# ASD2303.net
KiCad netlist of a schematic drawn in EAGLE
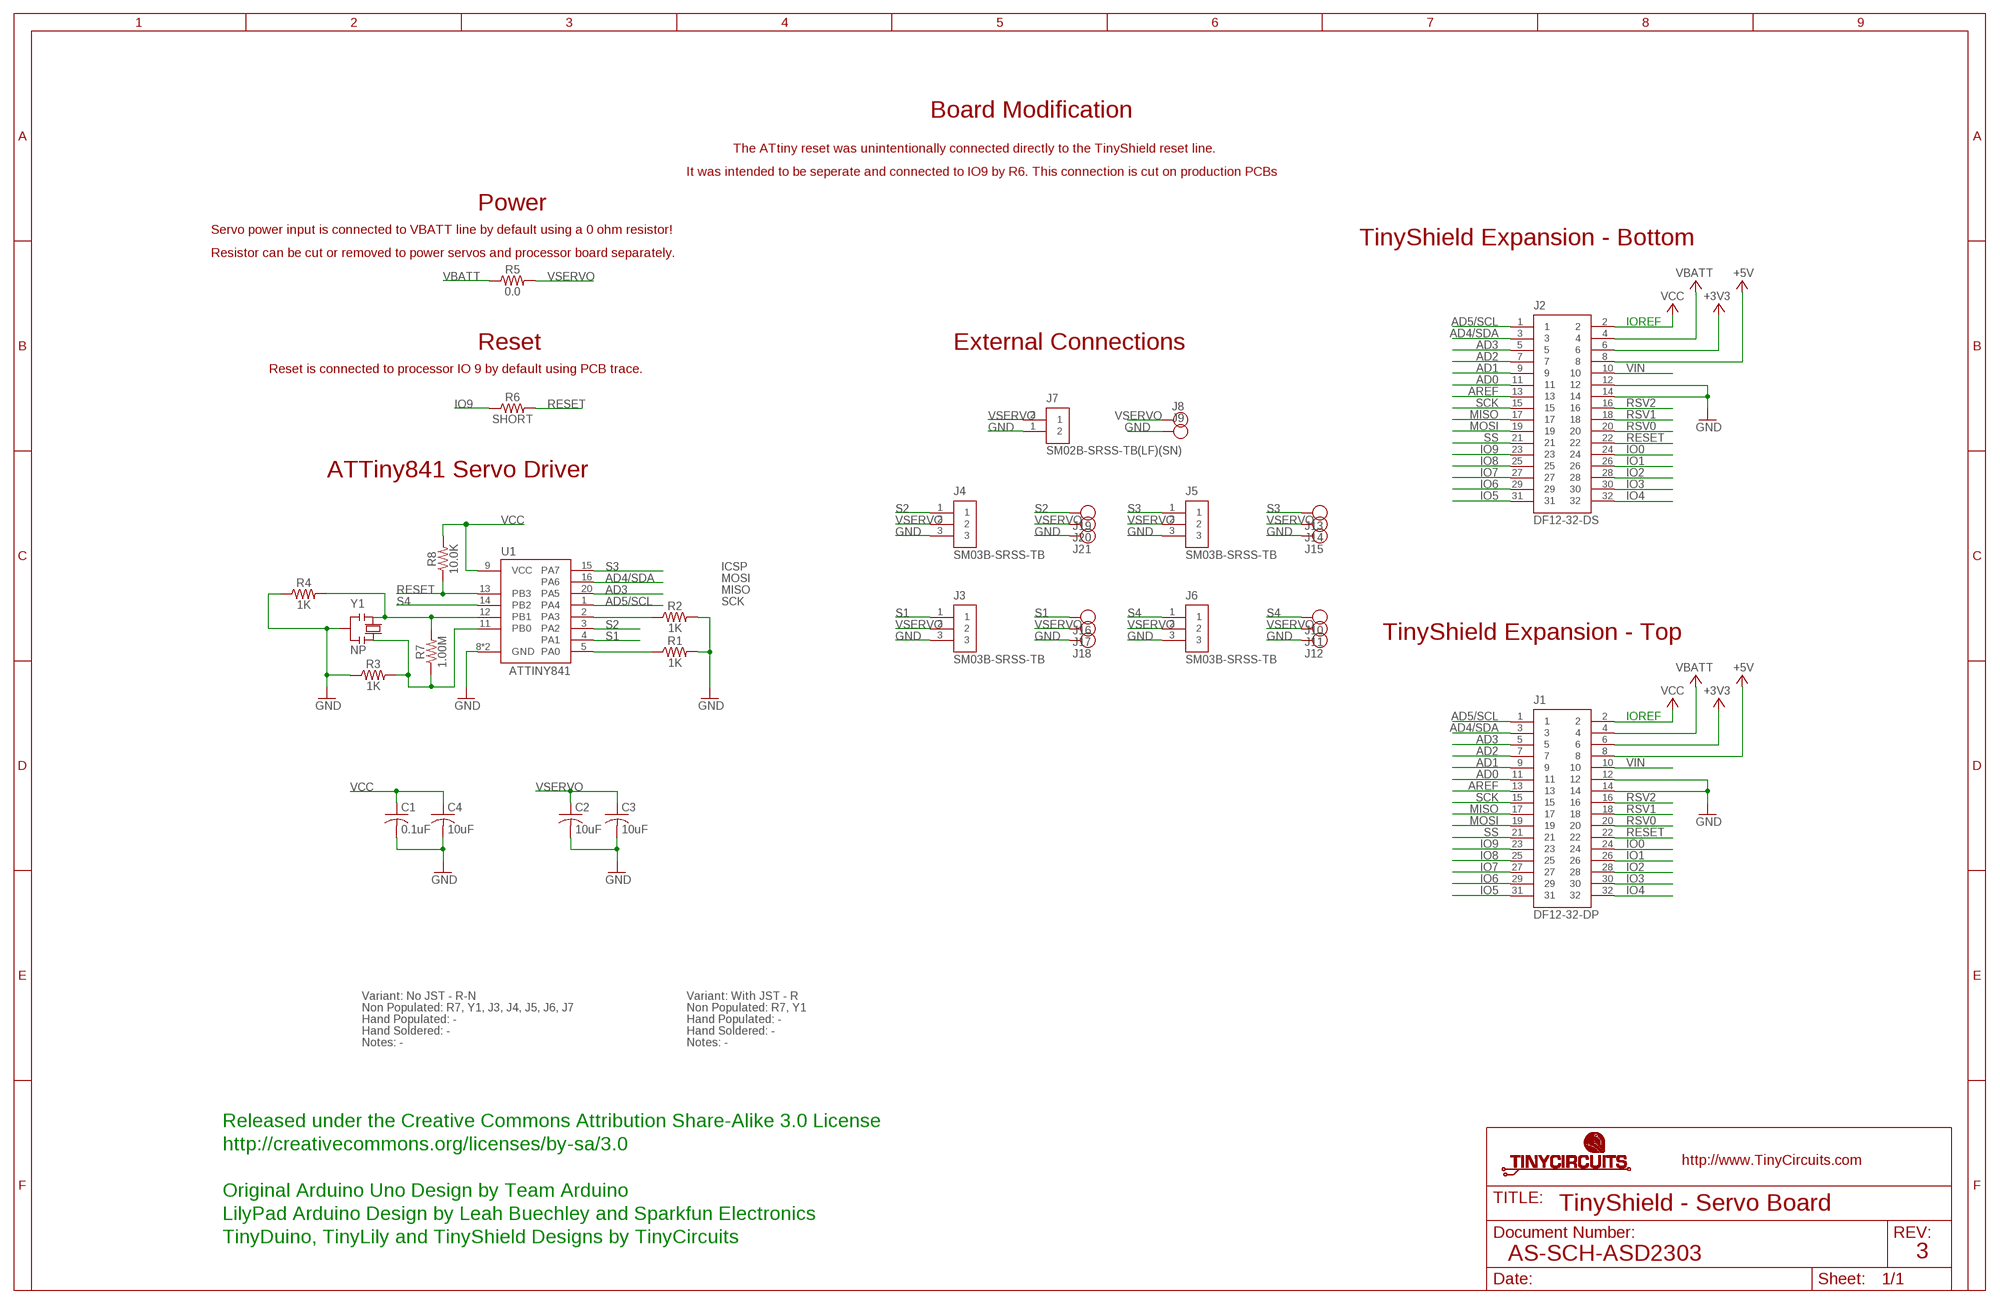
[diagram p0: schematic, sheet 1]

(export (version "E")
  (design (tool "Eeschema 10.0.6"))
  (components
    (comp (ref "C1")
      (value "0.1uF")
      (footprint "eagle-import:C0402")
      (fields (field (name "PARTNO") "AS-ITM-00008"))
      (libsource (lib "eagle-import") (part "AS-ITM-00008"))
    )
    (comp (ref "C2")
      (value "10uF")
      (footprint "eagle-import:C0805")
      (fields (field (name "PARTNO") "AS-ITM-00045"))
      (libsource (lib "eagle-import") (part "AS-ITM-00045"))
    )
    (comp (ref "C3")
      (value "10uF")
      (footprint "eagle-import:C0805")
      (fields (field (name "PARTNO") "AS-ITM-00045"))
      (libsource (lib "eagle-import") (part "AS-ITM-00045"))
    )
    (comp (ref "C4")
      (value "10uF")
      (footprint "eagle-import:C0805")
      (fields (field (name "PARTNO") "AS-ITM-00045"))
      (libsource (lib "eagle-import") (part "AS-ITM-00045"))
    )
    (comp (ref "J1")
      (value "DF12-32-DP")
      (footprint "eagle-import:DF12-32-DP")
      (fields (field (name "PARTNO") "AS-ITM-00015") (field (name "PARTNO_1") "AS-ITM-00015"))
      (libsource (lib "eagle-import") (part "AS-ITM-00015"))
    )
    (comp (ref "J2")
      (value "DF12-32-DS")
      (footprint "eagle-import:DF12-32-DS")
      (fields (field (name "PARTNO") "AS-ITM-00012") (field (name "PARTNO_1") "AS-ITM-00012"))
      (libsource (lib "eagle-import") (part "AS-ITM-00012"))
    )
    (comp (ref "J3")
      (value "SM03B-SRSS-TB")
      (footprint "eagle-import:JST_SH_3X1")
      (fields (field (name "PARTNO") "AS-ITM-00244"))
      (libsource (lib "eagle-import") (part "AS-ITM-00244"))
    )
    (comp (ref "J4")
      (value "SM03B-SRSS-TB")
      (footprint "eagle-import:JST_SH_3X1")
      (fields (field (name "PARTNO") "AS-ITM-00244"))
      (libsource (lib "eagle-import") (part "AS-ITM-00244"))
    )
    (comp (ref "J5")
      (value "SM03B-SRSS-TB")
      (footprint "eagle-import:JST_SH_3X1")
      (fields (field (name "PARTNO") "AS-ITM-00244"))
      (libsource (lib "eagle-import") (part "AS-ITM-00244"))
    )
    (comp (ref "J6")
      (value "SM03B-SRSS-TB")
      (footprint "eagle-import:JST_SH_3X1")
      (fields (field (name "PARTNO") "AS-ITM-00244"))
      (libsource (lib "eagle-import") (part "AS-ITM-00244"))
    )
    (comp (ref "J7")
      (value "SM02B-SRSS-TB(LF)(SN)")
      (footprint "eagle-import:JST_SH_2X1")
      (fields (field (name "PARTNO") "AS-ITM-00231"))
      (libsource (lib "eagle-import") (part "AS-ITM-00231"))
    )
    (comp (ref "J8")
      (value "PIN_1X.1\"1")
      (footprint "eagle-import:1X.1__2")
      (libsource (lib "eagle-import") (part "PIN_1X.1{dblquote}1"))
    )
    (comp (ref "J9")
      (value "PIN_1X.1\"1")
      (footprint "eagle-import:1X.1__2")
      (libsource (lib "eagle-import") (part "PIN_1X.1{dblquote}1"))
    )
    (comp (ref "J10")
      (value "PIN_1X.1\"1")
      (footprint "eagle-import:1X.1__2")
      (libsource (lib "eagle-import") (part "PIN_1X.1{dblquote}1"))
    )
    (comp (ref "J11")
      (value "PIN_1X.1\"1")
      (footprint "eagle-import:1X.1__2")
      (libsource (lib "eagle-import") (part "PIN_1X.1{dblquote}1"))
    )
    (comp (ref "J12")
      (value "PIN_1X.1\"1")
      (footprint "eagle-import:1X.1__2")
      (libsource (lib "eagle-import") (part "PIN_1X.1{dblquote}1"))
    )
    (comp (ref "J13")
      (value "PIN_1X.1\"1")
      (footprint "eagle-import:1X.1__2")
      (libsource (lib "eagle-import") (part "PIN_1X.1{dblquote}1"))
    )
    (comp (ref "J14")
      (value "PIN_1X.1\"1")
      (footprint "eagle-import:1X.1__2")
      (libsource (lib "eagle-import") (part "PIN_1X.1{dblquote}1"))
    )
    (comp (ref "J15")
      (value "PIN_1X.1\"1")
      (footprint "eagle-import:1X.1__2")
      (libsource (lib "eagle-import") (part "PIN_1X.1{dblquote}1"))
    )
    (comp (ref "J16")
      (value "PIN_1X.1\"1")
      (footprint "eagle-import:1X.1__2")
      (libsource (lib "eagle-import") (part "PIN_1X.1{dblquote}1"))
    )
    (comp (ref "J17")
      (value "PIN_1X.1\"1")
      (footprint "eagle-import:1X.1__2")
      (libsource (lib "eagle-import") (part "PIN_1X.1{dblquote}1"))
    )
    (comp (ref "J18")
      (value "PIN_1X.1\"1")
      (footprint "eagle-import:1X.1__2")
      (libsource (lib "eagle-import") (part "PIN_1X.1{dblquote}1"))
    )
    (comp (ref "J19")
      (value "PIN_1X.1\"1")
      (footprint "eagle-import:1X.1__2")
      (libsource (lib "eagle-import") (part "PIN_1X.1{dblquote}1"))
    )
    (comp (ref "J20")
      (value "PIN_1X.1\"1")
      (footprint "eagle-import:1X.1__2")
      (libsource (lib "eagle-import") (part "PIN_1X.1{dblquote}1"))
    )
    (comp (ref "J21")
      (value "PIN_1X.1\"1")
      (footprint "eagle-import:1X.1__2")
      (libsource (lib "eagle-import") (part "PIN_1X.1{dblquote}1"))
    )
    (comp (ref "R1")
      (value "1K")
      (footprint "eagle-import:0402")
      (fields (field (name "PARTNO") "AS-ITM-00003") (field (name "PARTNO_1") "AS-ITM-00003"))
      (libsource (lib "eagle-import") (part "AS-ITM-00003"))
    )
    (comp (ref "R2")
      (value "1K")
      (footprint "eagle-import:0402")
      (fields (field (name "PARTNO") "AS-ITM-00003") (field (name "PARTNO_1") "AS-ITM-00003"))
      (libsource (lib "eagle-import") (part "AS-ITM-00003"))
    )
    (comp (ref "R3")
      (value "1K")
      (footprint "eagle-import:0402")
      (fields (field (name "PARTNO") "AS-ITM-00003") (field (name "PARTNO_1") "AS-ITM-00003"))
      (libsource (lib "eagle-import") (part "AS-ITM-00003"))
    )
    (comp (ref "R4")
      (value "1K")
      (footprint "eagle-import:0402")
      (fields (field (name "PARTNO") "AS-ITM-00003") (field (name "PARTNO_1") "AS-ITM-00003"))
      (libsource (lib "eagle-import") (part "AS-ITM-00003"))
    )
    (comp (ref "R5")
      (value "0.0")
      (footprint "eagle-import:0402")
      (fields (field (name "PARTNO") "AS-ITM-00076"))
      (libsource (lib "eagle-import") (part "AS-ITM-00076"))
    )
    (comp (ref "R6")
      (value "SHORT")
      (footprint "eagle-import:0402_SHORT")
      (libsource (lib "eagle-import") (part "AS-ITM-000760402_SHORT"))
    )
    (comp (ref "R7")
      (value "1.00M")
      (footprint "eagle-import:0402")
      (fields (field (name "PARTNO") "AS-ITM-00005"))
      (libsource (lib "eagle-import") (part "AS-ITM-00005"))
    )
    (comp (ref "R8")
      (value "10.0K")
      (footprint "eagle-import:0402")
      (fields (field (name "PARTNO") "AS-ITM-00032"))
      (libsource (lib "eagle-import") (part "AS-ITM-00032"))
    )
    (comp (ref "U1")
      (value "ATTINY841")
      (footprint "eagle-import:VQFN-20")
      (fields (field (name "PARTNO") "AS-ITM-00255"))
      (libsource (lib "eagle-import") (part "AS-ITM-00255"))
    )
    (comp (ref "Y1")
      (value "NP")
      (footprint "eagle-import:RESONATOR_SMALL")
      (fields (field (name "PARTNO") "AS-ITM-00027") (field (name "PARTNO_1") "AS-ITM-00027"))
      (libsource (lib "eagle-import") (part "AS-ITM-00027B"))
    )
  )
  (nets
    (net (code "1") (name "+3V3") (class "Default")
      (node (ref "J1") (pin "6") (pinfunction "6_6") (pintype "bidirectional"))
      (node (ref "J2") (pin "6") (pinfunction "6_6") (pintype "bidirectional"))
    )
    (net (code "2") (name "+5V") (class "Default")
      (node (ref "J1") (pin "8") (pinfunction "8_8") (pintype "bidirectional"))
      (node (ref "J2") (pin "8") (pinfunction "8_8") (pintype "bidirectional"))
    )
    (net (code "3") (name "/AD0") (class "Default")
      (node (ref "J1") (pin "11") (pinfunction "11_11") (pintype "bidirectional"))
      (node (ref "J2") (pin "11") (pinfunction "11_11") (pintype "bidirectional"))
    )
    (net (code "4") (name "/AD1") (class "Default")
      (node (ref "J1") (pin "9") (pinfunction "9_9") (pintype "bidirectional"))
      (node (ref "J2") (pin "9") (pinfunction "9_9") (pintype "bidirectional"))
    )
    (net (code "5") (name "/AD2") (class "Default")
      (node (ref "J1") (pin "7") (pinfunction "7_7") (pintype "bidirectional"))
      (node (ref "J2") (pin "7") (pinfunction "7_7") (pintype "bidirectional"))
    )
    (net (code "6") (name "/AD3") (class "Default")
      (node (ref "J1") (pin "5") (pinfunction "5_5") (pintype "bidirectional"))
      (node (ref "J2") (pin "5") (pinfunction "5_5") (pintype "bidirectional"))
      (node (ref "U1") (pin "20") (pinfunction "PA5_20") (pintype "bidirectional"))
    )
    (net (code "7") (name "/AD4{slash}SDA") (class "Default")
      (node (ref "J1") (pin "3") (pinfunction "3_3") (pintype "bidirectional"))
      (node (ref "J2") (pin "3") (pinfunction "3_3") (pintype "bidirectional"))
      (node (ref "U1") (pin "16") (pinfunction "PA6_16") (pintype "bidirectional"))
    )
    (net (code "8") (name "/AD5{slash}SCL") (class "Default")
      (node (ref "J1") (pin "1") (pinfunction "1_1") (pintype "bidirectional"))
      (node (ref "J2") (pin "1") (pinfunction "1_1") (pintype "bidirectional"))
      (node (ref "U1") (pin "1") (pinfunction "PA4_1") (pintype "bidirectional"))
    )
    (net (code "9") (name "/AREF") (class "Default")
      (node (ref "J1") (pin "13") (pinfunction "13_13") (pintype "bidirectional"))
      (node (ref "J2") (pin "13") (pinfunction "13_13") (pintype "bidirectional"))
    )
    (net (code "10") (name "/IO0") (class "Default")
      (node (ref "J1") (pin "24") (pinfunction "24_24") (pintype "bidirectional"))
      (node (ref "J2") (pin "24") (pinfunction "24_24") (pintype "bidirectional"))
    )
    (net (code "11") (name "/IO1") (class "Default")
      (node (ref "J1") (pin "26") (pinfunction "26_26") (pintype "bidirectional"))
      (node (ref "J2") (pin "26") (pinfunction "26_26") (pintype "bidirectional"))
    )
    (net (code "12") (name "/IO2") (class "Default")
      (node (ref "J1") (pin "28") (pinfunction "28_28") (pintype "bidirectional"))
      (node (ref "J2") (pin "28") (pinfunction "28_28") (pintype "bidirectional"))
    )
    (net (code "13") (name "/IO3") (class "Default")
      (node (ref "J1") (pin "30") (pinfunction "30_30") (pintype "bidirectional"))
      (node (ref "J2") (pin "30") (pinfunction "30_30") (pintype "bidirectional"))
    )
    (net (code "14") (name "/IO4") (class "Default")
      (node (ref "J1") (pin "32") (pinfunction "32_32") (pintype "bidirectional"))
      (node (ref "J2") (pin "32") (pinfunction "32_32") (pintype "bidirectional"))
    )
    (net (code "15") (name "/IO5") (class "Default")
      (node (ref "J1") (pin "31") (pinfunction "31_31") (pintype "bidirectional"))
      (node (ref "J2") (pin "31") (pinfunction "31_31") (pintype "bidirectional"))
    )
    (net (code "16") (name "/IO6") (class "Default")
      (node (ref "J1") (pin "29") (pinfunction "29_29") (pintype "bidirectional"))
      (node (ref "J2") (pin "29") (pinfunction "29_29") (pintype "bidirectional"))
    )
    (net (code "17") (name "/IO7") (class "Default")
      (node (ref "J1") (pin "27") (pinfunction "27_27") (pintype "bidirectional"))
      (node (ref "J2") (pin "27") (pinfunction "27_27") (pintype "bidirectional"))
    )
    (net (code "18") (name "/IO8") (class "Default")
      (node (ref "J1") (pin "25") (pinfunction "25_25") (pintype "bidirectional"))
      (node (ref "J2") (pin "25") (pinfunction "25_25") (pintype "bidirectional"))
    )
    (net (code "19") (name "/IO9") (class "Default")
      (node (ref "J1") (pin "23") (pinfunction "23_23") (pintype "bidirectional"))
      (node (ref "J2") (pin "23") (pinfunction "23_23") (pintype "bidirectional"))
      (node (ref "R6") (pin "1") (pinfunction "1_1") (pintype "passive"))
    )
    (net (code "20") (name "/MISO") (class "Default")
      (node (ref "J1") (pin "17") (pinfunction "17_17") (pintype "bidirectional"))
      (node (ref "J2") (pin "17") (pinfunction "17_17") (pintype "bidirectional"))
    )
    (net (code "21") (name "/MOSI") (class "Default")
      (node (ref "J1") (pin "19") (pinfunction "19_19") (pintype "bidirectional"))
      (node (ref "J2") (pin "19") (pinfunction "19_19") (pintype "bidirectional"))
    )
    (net (code "22") (name "/RESET") (class "Default")
      (node (ref "J1") (pin "22") (pinfunction "22_22") (pintype "bidirectional"))
      (node (ref "J2") (pin "22") (pinfunction "22_22") (pintype "bidirectional"))
      (node (ref "R6") (pin "2") (pinfunction "2_2") (pintype "passive"))
      (node (ref "R8") (pin "1") (pinfunction "1_1") (pintype "passive"))
      (node (ref "U1") (pin "13") (pinfunction "PB3_13") (pintype "bidirectional"))
    )
    (net (code "23") (name "/RSV0") (class "Default")
      (node (ref "J1") (pin "20") (pinfunction "20_20") (pintype "bidirectional"))
      (node (ref "J2") (pin "20") (pinfunction "20_20") (pintype "bidirectional"))
    )
    (net (code "24") (name "/RSV1") (class "Default")
      (node (ref "J1") (pin "18") (pinfunction "18_18") (pintype "bidirectional"))
      (node (ref "J2") (pin "18") (pinfunction "18_18") (pintype "bidirectional"))
    )
    (net (code "25") (name "/RSV2") (class "Default")
      (node (ref "J1") (pin "16") (pinfunction "16_16") (pintype "bidirectional"))
      (node (ref "J2") (pin "16") (pinfunction "16_16") (pintype "bidirectional"))
    )
    (net (code "26") (name "/S1") (class "Default")
      (node (ref "J16") (pin "1") (pinfunction "1_1") (pintype "bidirectional"))
      (node (ref "J3") (pin "1") (pinfunction "1_1") (pintype "bidirectional"))
      (node (ref "U1") (pin "4") (pinfunction "PA1_4") (pintype "bidirectional"))
    )
    (net (code "27") (name "/S2") (class "Default")
      (node (ref "J19") (pin "1") (pinfunction "1_1") (pintype "bidirectional"))
      (node (ref "J4") (pin "1") (pinfunction "1_1") (pintype "bidirectional"))
      (node (ref "U1") (pin "3") (pinfunction "PA2_3") (pintype "bidirectional"))
    )
    (net (code "28") (name "/S3") (class "Default")
      (node (ref "J13") (pin "1") (pinfunction "1_1") (pintype "bidirectional"))
      (node (ref "J5") (pin "1") (pinfunction "1_1") (pintype "bidirectional"))
      (node (ref "U1") (pin "15") (pinfunction "PA7_15") (pintype "bidirectional"))
    )
    (net (code "29") (name "/S4") (class "Default")
      (node (ref "J10") (pin "1") (pinfunction "1_1") (pintype "bidirectional"))
      (node (ref "J6") (pin "1") (pinfunction "1_1") (pintype "bidirectional"))
      (node (ref "U1") (pin "14") (pinfunction "PB2_14") (pintype "bidirectional"))
    )
    (net (code "30") (name "/SCK") (class "Default")
      (node (ref "J1") (pin "15") (pinfunction "15_15") (pintype "bidirectional"))
      (node (ref "J2") (pin "15") (pinfunction "15_15") (pintype "bidirectional"))
    )
    (net (code "31") (name "/SS") (class "Default")
      (node (ref "J1") (pin "21") (pinfunction "21_21") (pintype "bidirectional"))
      (node (ref "J2") (pin "21") (pinfunction "21_21") (pintype "bidirectional"))
    )
    (net (code "32") (name "/VIN") (class "Default")
      (node (ref "J1") (pin "10") (pinfunction "10_10") (pintype "bidirectional"))
      (node (ref "J2") (pin "10") (pinfunction "10_10") (pintype "bidirectional"))
    )
    (net (code "33") (name "/VSERVO") (class "Default")
      (node (ref "C2") (pin "1") (pinfunction "1_1") (pintype "passive"))
      (node (ref "C3") (pin "1") (pinfunction "1_1") (pintype "passive"))
      (node (ref "J11") (pin "1") (pinfunction "1_1") (pintype "bidirectional"))
      (node (ref "J14") (pin "1") (pinfunction "1_1") (pintype "bidirectional"))
      (node (ref "J17") (pin "1") (pinfunction "1_1") (pintype "bidirectional"))
      (node (ref "J20") (pin "1") (pinfunction "1_1") (pintype "bidirectional"))
      (node (ref "J3") (pin "2") (pinfunction "2_2") (pintype "bidirectional"))
      (node (ref "J4") (pin "2") (pinfunction "2_2") (pintype "bidirectional"))
      (node (ref "J5") (pin "2") (pinfunction "2_2") (pintype "bidirectional"))
      (node (ref "J6") (pin "2") (pinfunction "2_2") (pintype "bidirectional"))
      (node (ref "J7") (pin "2") (pinfunction "1_2") (pintype "bidirectional"))
      (node (ref "J8") (pin "1") (pinfunction "1_1") (pintype "bidirectional"))
      (node (ref "R5") (pin "2") (pinfunction "2_2") (pintype "passive"))
    )
    (net (code "34") (name "GND") (class "Default")
      (node (ref "C1") (pin "2") (pinfunction "2_2") (pintype "passive"))
      (node (ref "C2") (pin "2") (pinfunction "2_2") (pintype "passive"))
      (node (ref "C3") (pin "2") (pinfunction "2_2") (pintype "passive"))
      (node (ref "C4") (pin "2") (pinfunction "2_2") (pintype "passive"))
      (node (ref "J1") (pin "12") (pinfunction "12_12") (pintype "bidirectional"))
      (node (ref "J1") (pin "14") (pinfunction "14_14") (pintype "bidirectional"))
      (node (ref "J12") (pin "1") (pinfunction "1_1") (pintype "bidirectional"))
      (node (ref "J15") (pin "1") (pinfunction "1_1") (pintype "bidirectional"))
      (node (ref "J18") (pin "1") (pinfunction "1_1") (pintype "bidirectional"))
      (node (ref "J2") (pin "12") (pinfunction "12_12") (pintype "bidirectional"))
      (node (ref "J2") (pin "14") (pinfunction "14_14") (pintype "bidirectional"))
      (node (ref "J21") (pin "1") (pinfunction "1_1") (pintype "bidirectional"))
      (node (ref "J3") (pin "3") (pinfunction "3_3") (pintype "bidirectional"))
      (node (ref "J4") (pin "3") (pinfunction "3_3") (pintype "bidirectional"))
      (node (ref "J5") (pin "3") (pinfunction "3_3") (pintype "bidirectional"))
      (node (ref "J6") (pin "3") (pinfunction "3_3") (pintype "bidirectional"))
      (node (ref "J7") (pin "1") (pinfunction "2_1") (pintype "bidirectional"))
      (node (ref "J9") (pin "1") (pinfunction "1_1") (pintype "bidirectional"))
      (node (ref "R1") (pin "2") (pinfunction "2_2") (pintype "passive"))
      (node (ref "R2") (pin "2") (pinfunction "2_2") (pintype "passive"))
      (node (ref "R3") (pin "1") (pinfunction "1_1") (pintype "passive"))
      (node (ref "R4") (pin "1") (pinfunction "1_1") (pintype "passive"))
      (node (ref "U1") (pin "8") (pinfunction "GND_8") (pintype "bidirectional"))
      (node (ref "U1") (pin "PAD") (pinfunction "GND_PAD") (pintype "bidirectional"))
      (node (ref "Y1") (pin "2") (pinfunction "2_2") (pintype "passive"))
    )
    (net (code "35") (name "Net-(U1-PA0)") (class "Default")
      (node (ref "R1") (pin "1") (pinfunction "1_1") (pintype "passive"))
      (node (ref "U1") (pin "5") (pinfunction "PA0_5") (pintype "bidirectional"))
    )
    (net (code "36") (name "Net-(U1-PA3)") (class "Default")
      (node (ref "R2") (pin "1") (pinfunction "1_1") (pintype "passive"))
      (node (ref "U1") (pin "2") (pinfunction "PA3_2") (pintype "bidirectional"))
    )
    (net (code "37") (name "Net-(U1-PB0)") (class "Default")
      (node (ref "R3") (pin "2") (pinfunction "2_2") (pintype "passive"))
      (node (ref "R7") (pin "1") (pinfunction "1_1") (pintype "passive"))
      (node (ref "U1") (pin "11") (pinfunction "PB0_11") (pintype "bidirectional"))
      (node (ref "Y1") (pin "3") (pinfunction "3_3") (pintype "passive"))
    )
    (net (code "38") (name "Net-(U1-PB1)") (class "Default")
      (node (ref "R4") (pin "2") (pinfunction "2_2") (pintype "passive"))
      (node (ref "R7") (pin "2") (pinfunction "2_2") (pintype "passive"))
      (node (ref "U1") (pin "12") (pinfunction "PB1_12") (pintype "bidirectional"))
      (node (ref "Y1") (pin "1") (pinfunction "1_1") (pintype "passive"))
    )
    (net (code "39") (name "VBATT") (class "Default")
      (node (ref "J1") (pin "4") (pinfunction "4_4") (pintype "bidirectional"))
      (node (ref "J2") (pin "4") (pinfunction "4_4") (pintype "bidirectional"))
      (node (ref "R5") (pin "1") (pinfunction "1_1") (pintype "passive"))
    )
    (net (code "40") (name "VCC") (class "Default")
      (node (ref "C1") (pin "1") (pinfunction "1_1") (pintype "passive"))
      (node (ref "C4") (pin "1") (pinfunction "1_1") (pintype "passive"))
      (node (ref "J1") (pin "2") (pinfunction "2_2") (pintype "bidirectional"))
      (node (ref "J2") (pin "2") (pinfunction "2_2") (pintype "bidirectional"))
      (node (ref "R8") (pin "2") (pinfunction "2_2") (pintype "passive"))
      (node (ref "U1") (pin "9") (pinfunction "VCC_9") (pintype "bidirectional"))
    )
  )
)
